# Battery_Boost_Converter.net
KiCad netlist of a schematic drawn in Altium Designer
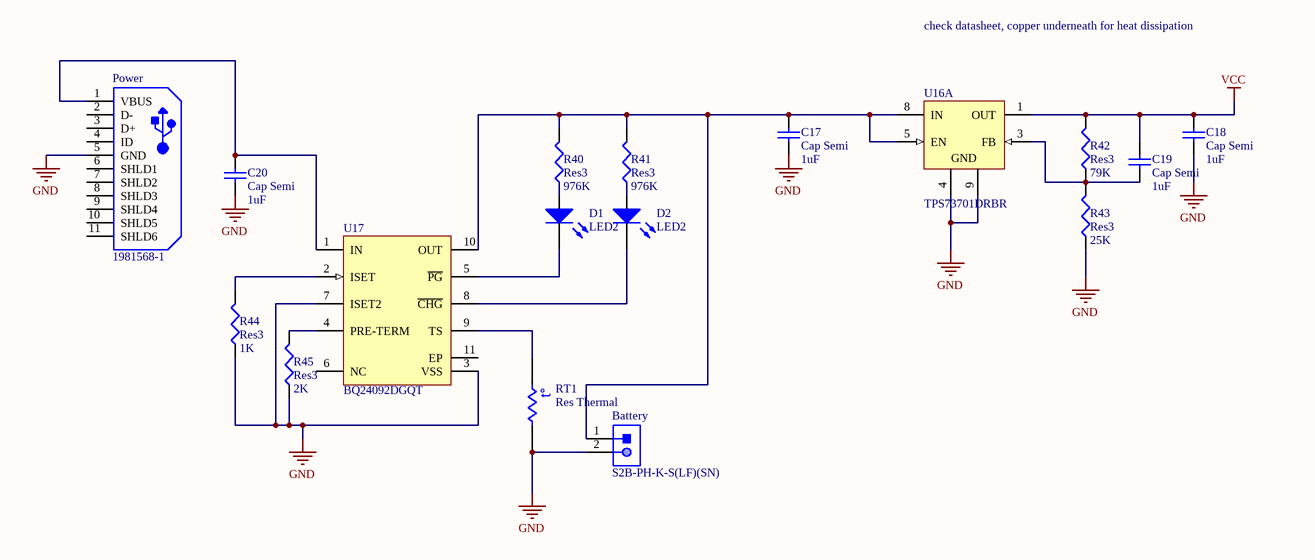
[diagram p0: Battery_Boost_Converter.SchDoc]

(export (version "E")
  (design (tool "Eeschema 10.0.6"))
  (components
    (comp (ref "Battery")
      (value "S2B-PH-K-S(LF)(SN)")
      (footprint "JST-S2B-PH-K-S_V")
      (fields (field (name "TOLERANCE") "20%"))
      (libsource (lib "Altium Content Vault") (part "CN-1P-M-R2"))
    )
    (comp (ref "C17")
      (value "Cap Semi")
      (footprint "C1206")
      (description "Capacitor (Semiconductor SIM Model)")
      (fields (field (name "ALTIUM_VALUE") "1uF") (field (name "PUBLISHER") "Altium Limited"))
      (libsource (lib "Miscellaneous Devices") (part "Cap Semi"))
    )
    (comp (ref "C18")
      (value "Cap Semi")
      (footprint "C1206")
      (description "Capacitor (Semiconductor SIM Model)")
      (fields (field (name "ALTIUM_VALUE") "1uF") (field (name "PUBLISHER") "Altium Limited"))
      (libsource (lib "Miscellaneous Devices") (part "Cap Semi"))
    )
    (comp (ref "C19")
      (value "Cap Semi")
      (footprint "C1206")
      (description "Capacitor (Semiconductor SIM Model)")
      (fields (field (name "ALTIUM_VALUE") "1uF") (field (name "PUBLISHER") "Altium Limited"))
      (libsource (lib "Miscellaneous Devices") (part "Cap Semi"))
    )
    (comp (ref "C20")
      (value "Cap Semi")
      (footprint "C1206")
      (description "Capacitor (Semiconductor SIM Model)")
      (fields (field (name "ALTIUM_VALUE") "1uF") (field (name "PUBLISHER") "Altium Limited"))
      (libsource (lib "Miscellaneous Devices") (part "Cap Semi"))
    )
    (comp (ref "D1")
      (value "LED2")
      (footprint "3.2X1.6X1.1")
      (description "Typical RED, GREEN, YELLOW, AMBER GaAs LED")
      (fields (field (name "PUBLISHER") "Altium Limited"))
      (libsource (lib "Miscellaneous Devices") (part "LED2"))
    )
    (comp (ref "D2")
      (value "LED2")
      (footprint "3.2X1.6X1.1")
      (description "Typical RED, GREEN, YELLOW, AMBER GaAs LED")
      (fields (field (name "PUBLISHER") "Altium Limited"))
      (libsource (lib "Miscellaneous Devices") (part "LED2"))
    )
    (comp (ref "Power")
      (value "1981568-1")
      (footprint "TECO-1981568-5_V")
      (description "Micro USB Receptacle Standard Type B Assy, 5-Pin SMD, RoHS, Tape and Reel")
      (fields (field (name "MANUFACTURER") "TE Connectivity"))
      (libsource (lib "Altium Content Vault") (part "USB-5-6SHLD"))
    )
    (comp (ref "R40")
      (value "Res3")
      (footprint "J1-0603")
      (description "Resistor")
      (fields (field (name "ALTIUM_VALUE") "976K") (field (name "PUBLISHER") "Altium Limited"))
      (libsource (lib "Miscellaneous Devices") (part "Res3"))
    )
    (comp (ref "R41")
      (value "Res3")
      (footprint "J1-0603")
      (description "Resistor")
      (fields (field (name "ALTIUM_VALUE") "976K") (field (name "PUBLISHER") "Altium Limited"))
      (libsource (lib "Miscellaneous Devices") (part "Res3"))
    )
    (comp (ref "R42")
      (value "Res3")
      (footprint "J1-0603")
      (description "Resistor")
      (fields (field (name "ALTIUM_VALUE") "79K") (field (name "PUBLISHER") "Altium Limited"))
      (libsource (lib "Miscellaneous Devices") (part "Res3"))
    )
    (comp (ref "R43")
      (value "Res3")
      (footprint "J1-0603")
      (description "Resistor")
      (fields (field (name "ALTIUM_VALUE") "25K") (field (name "PUBLISHER") "Altium Limited"))
      (libsource (lib "Miscellaneous Devices") (part "Res3"))
    )
    (comp (ref "R44")
      (value "Res3")
      (footprint "J1-0603")
      (description "Resistor")
      (fields (field (name "ALTIUM_VALUE") "1K") (field (name "PUBLISHER") "Altium Limited"))
      (libsource (lib "Miscellaneous Devices") (part "Res3"))
    )
    (comp (ref "R45")
      (value "Res3")
      (footprint "J1-0603")
      (description "Resistor")
      (fields (field (name "ALTIUM_VALUE") "2K") (field (name "PUBLISHER") "Altium Limited"))
      (libsource (lib "Miscellaneous Devices") (part "Res3"))
    )
    (comp (ref "RT1")
      (value "Res Thermal")
      (footprint "6-0805_N")
      (description "Thermistor")
      (fields (field (name "PUBLISHER") "Altium Limited"))
      (libsource (lib "Miscellaneous Devices") (part "Res Thermal"))
    )
    (comp (ref "U16")
      (value "TPS73701DRBR")
      (footprint "DRB0008A_V")
      (fields (field (name "MANUFACTURER") "Texas Instruments"))
      (libsource (lib "Altium Content Vault") (part "TI-TPS73701DRB8-1750X1500TP"))
    )
    (comp (ref "U17")
      (value "BQ24092DGQT")
      (footprint "DGQ0010D_L")
      (fields (field (name "MANUFACTURER") "Texas Instruments"))
      (libsource (lib "Altium Content Vault") (part "TI-BQ24092DGQ10-1675X1445TP"))
    )
  )
  (nets
    (net (code "1") (name "GND") (class "Default")
      (node (ref "Battery") (pin "2") (pinfunction "2_2") (pintype "passive"))
      (node (ref "C17") (pin "1") (pinfunction "1_1") (pintype "passive"))
      (node (ref "C18") (pin "1") (pinfunction "1_1") (pintype "passive"))
      (node (ref "C20") (pin "1") (pinfunction "1_1") (pintype "passive"))
      (node (ref "Power") (pin "5") (pinfunction "GND_5") (pintype "passive"))
      (node (ref "R43") (pin "1") (pinfunction "1_1") (pintype "passive"))
      (node (ref "R44") (pin "1") (pinfunction "1_1") (pintype "passive"))
      (node (ref "R45") (pin "1") (pinfunction "1_1") (pintype "passive"))
      (node (ref "RT1") (pin "2") (pinfunction "2_2") (pintype "passive"))
      (node (ref "U16") (pin "4") (pinfunction "GND_4") (pintype "power_in"))
      (node (ref "U16") (pin "9") (pinfunction "GND_9") (pintype "power_in"))
      (node (ref "U17") (pin "3") (pinfunction "VSS_3") (pintype "power_in"))
      (node (ref "U17") (pin "7") (pinfunction "ISET2_7") (pintype "passive"))
    )
    (net (code "2") (name "Net-(D1-A)") (class "Default")
      (node (ref "D1") (pin "1") (pinfunction "A_1") (pintype "passive"))
      (node (ref "R40") (pin "1") (pinfunction "1_1") (pintype "passive"))
    )
    (net (code "3") (name "Net-(D1-K)") (class "Default")
      (node (ref "D1") (pin "2") (pinfunction "K_2") (pintype "passive"))
      (node (ref "U17") (pin "5") (pinfunction "~{PG}_5") (pintype "tri_state"))
    )
    (net (code "4") (name "Net-(D2-A)") (class "Default")
      (node (ref "D2") (pin "1") (pinfunction "A_1") (pintype "passive"))
      (node (ref "R41") (pin "1") (pinfunction "1_1") (pintype "passive"))
    )
    (net (code "5") (name "Net-(D2-K)") (class "Default")
      (node (ref "D2") (pin "2") (pinfunction "K_2") (pintype "passive"))
      (node (ref "U17") (pin "8") (pinfunction "~{CHG}_8") (pintype "tri_state"))
    )
    (net (code "6") (name "Net-(Power-VBUS)") (class "Default")
      (node (ref "C20") (pin "2") (pinfunction "2_2") (pintype "passive"))
      (node (ref "Power") (pin "1") (pinfunction "VBUS_1") (pintype "passive"))
      (node (ref "U17") (pin "1") (pinfunction "IN_1") (pintype "power_in"))
    )
    (net (code "7") (name "Net-(U16A-EN)") (class "Default")
      (node (ref "Battery") (pin "1") (pinfunction "1_1") (pintype "passive"))
      (node (ref "C17") (pin "2") (pinfunction "2_2") (pintype "passive"))
      (node (ref "R40") (pin "2") (pinfunction "2_2") (pintype "passive"))
      (node (ref "R41") (pin "2") (pinfunction "2_2") (pintype "passive"))
      (node (ref "U16") (pin "5") (pinfunction "EN_5") (pintype "input"))
      (node (ref "U16") (pin "8") (pinfunction "IN_8") (pintype "power_in"))
      (node (ref "U17") (pin "10") (pinfunction "OUT_10") (pintype "power_in"))
    )
    (net (code "8") (name "Net-(U16A-FB)") (class "Default")
      (node (ref "C19") (pin "1") (pinfunction "1_1") (pintype "passive"))
      (node (ref "R42") (pin "1") (pinfunction "1_1") (pintype "passive"))
      (node (ref "R43") (pin "2") (pinfunction "2_2") (pintype "passive"))
      (node (ref "U16") (pin "3") (pinfunction "FB_3") (pintype "input"))
    )
    (net (code "9") (name "Net-(U17-ISET)") (class "Default")
      (node (ref "R44") (pin "2") (pinfunction "2_2") (pintype "passive"))
      (node (ref "U17") (pin "2") (pinfunction "ISET_2") (pintype "input"))
    )
    (net (code "10") (name "Net-(U17-PRE-TERM)") (class "Default")
      (node (ref "R45") (pin "2") (pinfunction "2_2") (pintype "passive"))
      (node (ref "U17") (pin "4") (pinfunction "PRE-TERM_4") (pintype "passive"))
    )
    (net (code "11") (name "Net-(U17-TS)") (class "Default")
      (node (ref "RT1") (pin "1") (pinfunction "1_1") (pintype "passive"))
      (node (ref "U17") (pin "9") (pinfunction "TS_9") (pintype "passive"))
    )
    (net (code "12") (name "VCC") (class "Default")
      (node (ref "C18") (pin "2") (pinfunction "2_2") (pintype "passive"))
      (node (ref "C19") (pin "2") (pinfunction "2_2") (pintype "passive"))
      (node (ref "R42") (pin "2") (pinfunction "2_2") (pintype "passive"))
      (node (ref "U16") (pin "1") (pinfunction "OUT_1") (pintype "power_in"))
    )
    (net (code "13") (name "unconnected-(Power-D+-Pad3)") (class "Default")
      (node (ref "Power") (pin "3") (pinfunction "D+_3") (pintype "passive"))
    )
    (net (code "14") (name "unconnected-(Power-D--Pad2)") (class "Default")
      (node (ref "Power") (pin "2") (pinfunction "D-_2") (pintype "passive"))
    )
    (net (code "15") (name "unconnected-(Power-ID-Pad4)") (class "Default")
      (node (ref "Power") (pin "4") (pinfunction "ID_4") (pintype "passive"))
    )
    (net (code "16") (name "unconnected-(Power-SHLD1-Pad6)") (class "Default")
      (node (ref "Power") (pin "6") (pinfunction "SHLD1_6") (pintype "passive"))
    )
    (net (code "17") (name "unconnected-(Power-SHLD2-Pad7)") (class "Default")
      (node (ref "Power") (pin "7") (pinfunction "SHLD2_7") (pintype "passive"))
    )
    (net (code "18") (name "unconnected-(Power-SHLD3-Pad8)") (class "Default")
      (node (ref "Power") (pin "8") (pinfunction "SHLD3_8") (pintype "passive"))
    )
    (net (code "19") (name "unconnected-(Power-SHLD4-Pad9)") (class "Default")
      (node (ref "Power") (pin "9") (pinfunction "SHLD4_9") (pintype "passive"))
    )
    (net (code "20") (name "unconnected-(Power-SHLD5-Pad10)") (class "Default")
      (node (ref "Power") (pin "10") (pinfunction "SHLD5_10") (pintype "passive"))
    )
    (net (code "21") (name "unconnected-(Power-SHLD6-Pad11)") (class "Default")
      (node (ref "Power") (pin "11") (pinfunction "SHLD6_11") (pintype "passive"))
    )
    (net (code "22") (name "unconnected-(U17-EP-Pad11)") (class "Default")
      (node (ref "U17") (pin "11") (pinfunction "EP_11") (pintype "power_in"))
    )
    (net (code "23") (name "unconnected-(U17-NC-Pad6)") (class "Default")
      (node (ref "U17") (pin "6") (pinfunction "NC_6") (pintype "passive"))
    )
  )
)
